# mux_smd.net
KiCad netlist of a schematic drawn in EAGLE
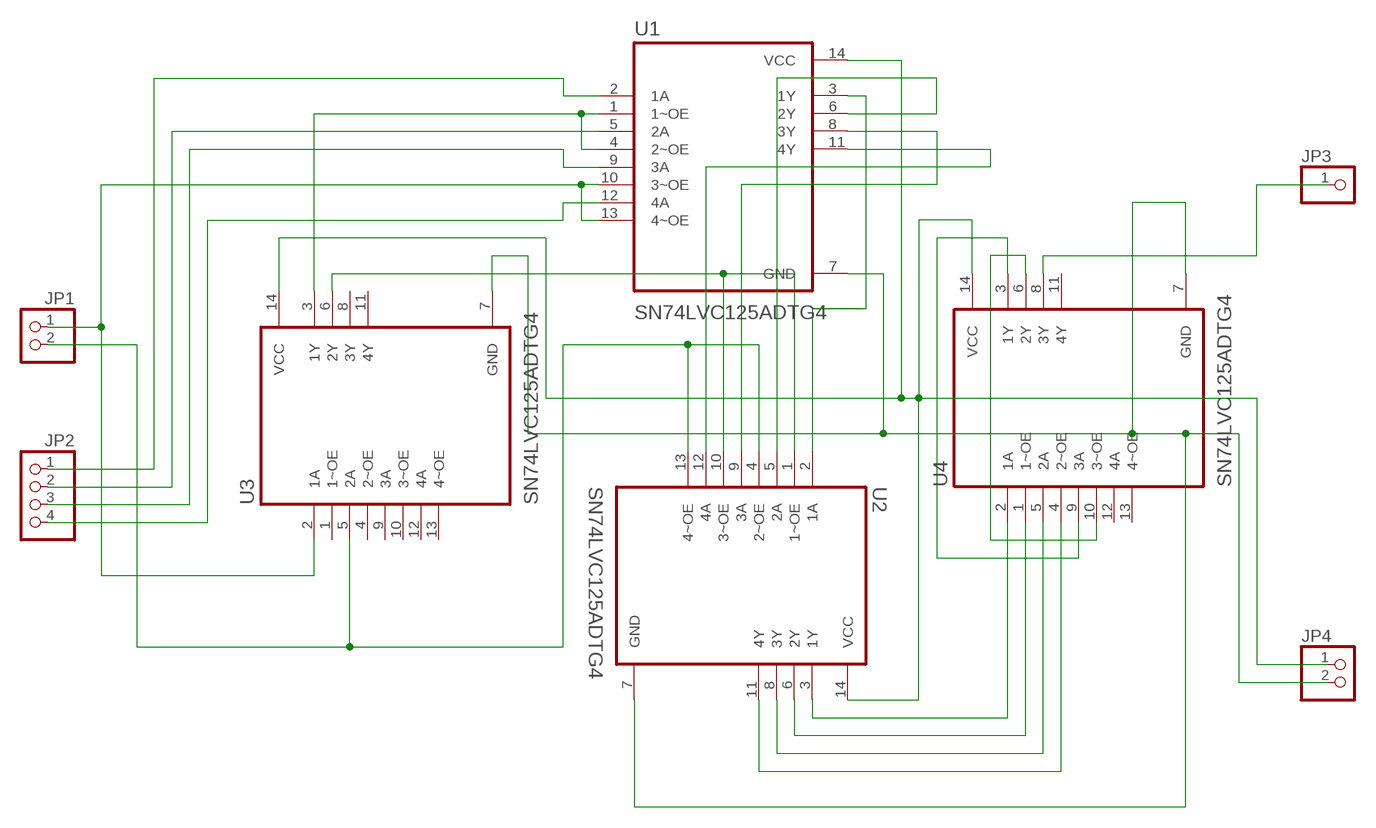
[diagram p0: schematic, sheet 1]

(export (version "E")
  (design (tool "Eeschema 10.0.6"))
  (components
    (comp (ref "JP1")
      (value "PINHD-1X2")
      (footprint "eagle-import:1X02")
      (libsource (lib "eagle-import") (part "PINHD-1X2"))
    )
    (comp (ref "JP2")
      (value "PINHD-1X4")
      (footprint "eagle-import:1X04")
      (libsource (lib "eagle-import") (part "PINHD-1X4"))
    )
    (comp (ref "JP3")
      (value "PINHD-1X1")
      (footprint "eagle-import:1X01")
      (libsource (lib "eagle-import") (part "PINHD-1X1"))
    )
    (comp (ref "JP4")
      (value "PINHD-1X2")
      (footprint "eagle-import:1X02")
      (libsource (lib "eagle-import") (part "PINHD-1X2"))
    )
    (comp (ref "U1")
      (value "SN74LVC125ADTG4")
      (footprint "eagle-import:SOIC127P600X175-14N")
      (fields (field (name "MF") "Texas Instruments"))
      (libsource (lib "eagle-import") (part "SN74LVC125ADTG4"))
    )
    (comp (ref "U2")
      (value "SN74LVC125ADTG4")
      (footprint "eagle-import:SOIC127P600X175-14N")
      (fields (field (name "MF") "Texas Instruments"))
      (libsource (lib "eagle-import") (part "SN74LVC125ADTG4"))
    )
    (comp (ref "U3")
      (value "SN74LVC125ADTG4")
      (footprint "eagle-import:SOIC127P600X175-14N")
      (fields (field (name "MF") "Texas Instruments"))
      (libsource (lib "eagle-import") (part "SN74LVC125ADTG4"))
    )
    (comp (ref "U4")
      (value "SN74LVC125ADTG4")
      (footprint "eagle-import:SOIC127P600X175-14N")
      (fields (field (name "MF") "Texas Instruments"))
      (libsource (lib "eagle-import") (part "SN74LVC125ADTG4"))
    )
  )
  (nets
    (net (code "1") (name "Net-(U1-1A)") (class "Default")
      (node (ref "JP2") (pin "1") (pinfunction "1_1") (pintype "passive"))
      (node (ref "U1") (pin "2") (pinfunction "1A_2") (pintype "input"))
    )
    (net (code "2") (name "Net-(U1-1Y)") (class "Default")
      (node (ref "U1") (pin "3") (pinfunction "1Y_3") (pintype "output"))
      (node (ref "U2") (pin "2") (pinfunction "1A_2") (pintype "input"))
    )
    (net (code "3") (name "Net-(U1-1~{OE})") (class "Default")
      (node (ref "U1") (pin "1") (pinfunction "1~{OE}_1") (pintype "input"))
      (node (ref "U1") (pin "4") (pinfunction "2~{OE}_4") (pintype "input"))
      (node (ref "U3") (pin "3") (pinfunction "1Y_3") (pintype "output"))
    )
    (net (code "4") (name "Net-(U1-2A)") (class "Default")
      (node (ref "JP2") (pin "2") (pinfunction "2_2") (pintype "passive"))
      (node (ref "U1") (pin "5") (pinfunction "2A_5") (pintype "input"))
    )
    (net (code "5") (name "Net-(U1-2Y)") (class "Default")
      (node (ref "U1") (pin "6") (pinfunction "2Y_6") (pintype "output"))
      (node (ref "U2") (pin "5") (pinfunction "2A_5") (pintype "input"))
    )
    (net (code "6") (name "Net-(U1-3A)") (class "Default")
      (node (ref "JP2") (pin "3") (pinfunction "3_3") (pintype "passive"))
      (node (ref "U1") (pin "9") (pinfunction "3A_9") (pintype "input"))
    )
    (net (code "7") (name "Net-(U1-3Y)") (class "Default")
      (node (ref "U1") (pin "8") (pinfunction "3Y_8") (pintype "output"))
      (node (ref "U2") (pin "9") (pinfunction "3A_9") (pintype "input"))
    )
    (net (code "8") (name "Net-(U1-3~{OE})") (class "Default")
      (node (ref "JP1") (pin "1") (pinfunction "1_1") (pintype "passive"))
      (node (ref "U1") (pin "10") (pinfunction "3~{OE}_10") (pintype "input"))
      (node (ref "U1") (pin "13") (pinfunction "4~{OE}_13") (pintype "input"))
      (node (ref "U3") (pin "2") (pinfunction "1A_2") (pintype "input"))
    )
    (net (code "9") (name "Net-(U1-4A)") (class "Default")
      (node (ref "JP2") (pin "4") (pinfunction "4_4") (pintype "passive"))
      (node (ref "U1") (pin "12") (pinfunction "4A_12") (pintype "input"))
    )
    (net (code "10") (name "Net-(U1-4Y)") (class "Default")
      (node (ref "U1") (pin "11") (pinfunction "4Y_11") (pintype "output"))
      (node (ref "U2") (pin "12") (pinfunction "4A_12") (pintype "input"))
    )
    (net (code "11") (name "Net-(U1-GND)") (class "Default")
      (node (ref "JP4") (pin "2") (pinfunction "2_2") (pintype "passive"))
      (node (ref "U1") (pin "7") (pinfunction "GND_7") (pintype "power_in"))
      (node (ref "U2") (pin "7") (pinfunction "GND_7") (pintype "power_in"))
      (node (ref "U3") (pin "7") (pinfunction "GND_7") (pintype "power_in"))
      (node (ref "U4") (pin "7") (pinfunction "GND_7") (pintype "power_in"))
    )
    (net (code "12") (name "Net-(U1-VCC)") (class "Default")
      (node (ref "JP4") (pin "1") (pinfunction "1_1") (pintype "passive"))
      (node (ref "U1") (pin "14") (pinfunction "VCC_14") (pintype "power_in"))
      (node (ref "U2") (pin "14") (pinfunction "VCC_14") (pintype "power_in"))
      (node (ref "U3") (pin "14") (pinfunction "VCC_14") (pintype "power_in"))
      (node (ref "U4") (pin "14") (pinfunction "VCC_14") (pintype "power_in"))
    )
    (net (code "13") (name "Net-(U2-1Y)") (class "Default")
      (node (ref "U2") (pin "3") (pinfunction "1Y_3") (pintype "output"))
      (node (ref "U4") (pin "2") (pinfunction "1A_2") (pintype "input"))
    )
    (net (code "14") (name "Net-(U2-1~{OE})") (class "Default")
      (node (ref "U2") (pin "1") (pinfunction "1~{OE}_1") (pintype "input"))
      (node (ref "U2") (pin "10") (pinfunction "3~{OE}_10") (pintype "input"))
      (node (ref "U3") (pin "6") (pinfunction "2Y_6") (pintype "output"))
    )
    (net (code "15") (name "Net-(U2-2Y)") (class "Default")
      (node (ref "U2") (pin "6") (pinfunction "2Y_6") (pintype "output"))
      (node (ref "U4") (pin "1") (pinfunction "1~{OE}_1") (pintype "input"))
    )
    (net (code "16") (name "Net-(U2-2~{OE})") (class "Default")
      (node (ref "JP1") (pin "2") (pinfunction "2_2") (pintype "passive"))
      (node (ref "U2") (pin "13") (pinfunction "4~{OE}_13") (pintype "input"))
      (node (ref "U2") (pin "4") (pinfunction "2~{OE}_4") (pintype "input"))
      (node (ref "U3") (pin "5") (pinfunction "2A_5") (pintype "input"))
    )
    (net (code "17") (name "Net-(U2-3Y)") (class "Default")
      (node (ref "U2") (pin "8") (pinfunction "3Y_8") (pintype "output"))
      (node (ref "U4") (pin "5") (pinfunction "2A_5") (pintype "input"))
    )
    (net (code "18") (name "Net-(U2-4Y)") (class "Default")
      (node (ref "U2") (pin "11") (pinfunction "4Y_11") (pintype "output"))
      (node (ref "U4") (pin "4") (pinfunction "2~{OE}_4") (pintype "input"))
    )
    (net (code "19") (name "Net-(U4-1Y)") (class "Default")
      (node (ref "U4") (pin "3") (pinfunction "1Y_3") (pintype "output"))
      (node (ref "U4") (pin "9") (pinfunction "3A_9") (pintype "input"))
    )
    (net (code "20") (name "Net-(U4-2Y)") (class "Default")
      (node (ref "U4") (pin "10") (pinfunction "3~{OE}_10") (pintype "input"))
      (node (ref "U4") (pin "6") (pinfunction "2Y_6") (pintype "output"))
    )
    (net (code "21") (name "Net-(U4-3Y)") (class "Default")
      (node (ref "JP3") (pin "1") (pinfunction "1_1") (pintype "passive"))
      (node (ref "U4") (pin "8") (pinfunction "3Y_8") (pintype "output"))
    )
    (net (code "22") (name "unconnected-(U3-1~{OE}-Pad1)") (class "Default")
      (node (ref "U3") (pin "1") (pinfunction "1~{OE}_1") (pintype "input"))
    )
    (net (code "23") (name "unconnected-(U3-2~{OE}-Pad4)") (class "Default")
      (node (ref "U3") (pin "4") (pinfunction "2~{OE}_4") (pintype "input"))
    )
    (net (code "24") (name "unconnected-(U3-3A-Pad9)") (class "Default")
      (node (ref "U3") (pin "9") (pinfunction "3A_9") (pintype "input"))
    )
    (net (code "25") (name "unconnected-(U3-3Y-Pad8)") (class "Default")
      (node (ref "U3") (pin "8") (pinfunction "3Y_8") (pintype "output"))
    )
    (net (code "26") (name "unconnected-(U3-3~{OE}-Pad10)") (class "Default")
      (node (ref "U3") (pin "10") (pinfunction "3~{OE}_10") (pintype "input"))
    )
    (net (code "27") (name "unconnected-(U3-4A-Pad12)") (class "Default")
      (node (ref "U3") (pin "12") (pinfunction "4A_12") (pintype "input"))
    )
    (net (code "28") (name "unconnected-(U3-4Y-Pad11)") (class "Default")
      (node (ref "U3") (pin "11") (pinfunction "4Y_11") (pintype "output"))
    )
    (net (code "29") (name "unconnected-(U3-4~{OE}-Pad13)") (class "Default")
      (node (ref "U3") (pin "13") (pinfunction "4~{OE}_13") (pintype "input"))
    )
    (net (code "30") (name "unconnected-(U4-4A-Pad12)") (class "Default")
      (node (ref "U4") (pin "12") (pinfunction "4A_12") (pintype "input"))
    )
    (net (code "31") (name "unconnected-(U4-4Y-Pad11)") (class "Default")
      (node (ref "U4") (pin "11") (pinfunction "4Y_11") (pintype "output"))
    )
    (net (code "32") (name "unconnected-(U4-4~{OE}-Pad13)") (class "Default")
      (node (ref "U4") (pin "13") (pinfunction "4~{OE}_13") (pintype "input"))
    )
  )
)
